# Motor_Control_-_Top_Level.net
KiCad netlist of a schematic drawn in Altium Designer
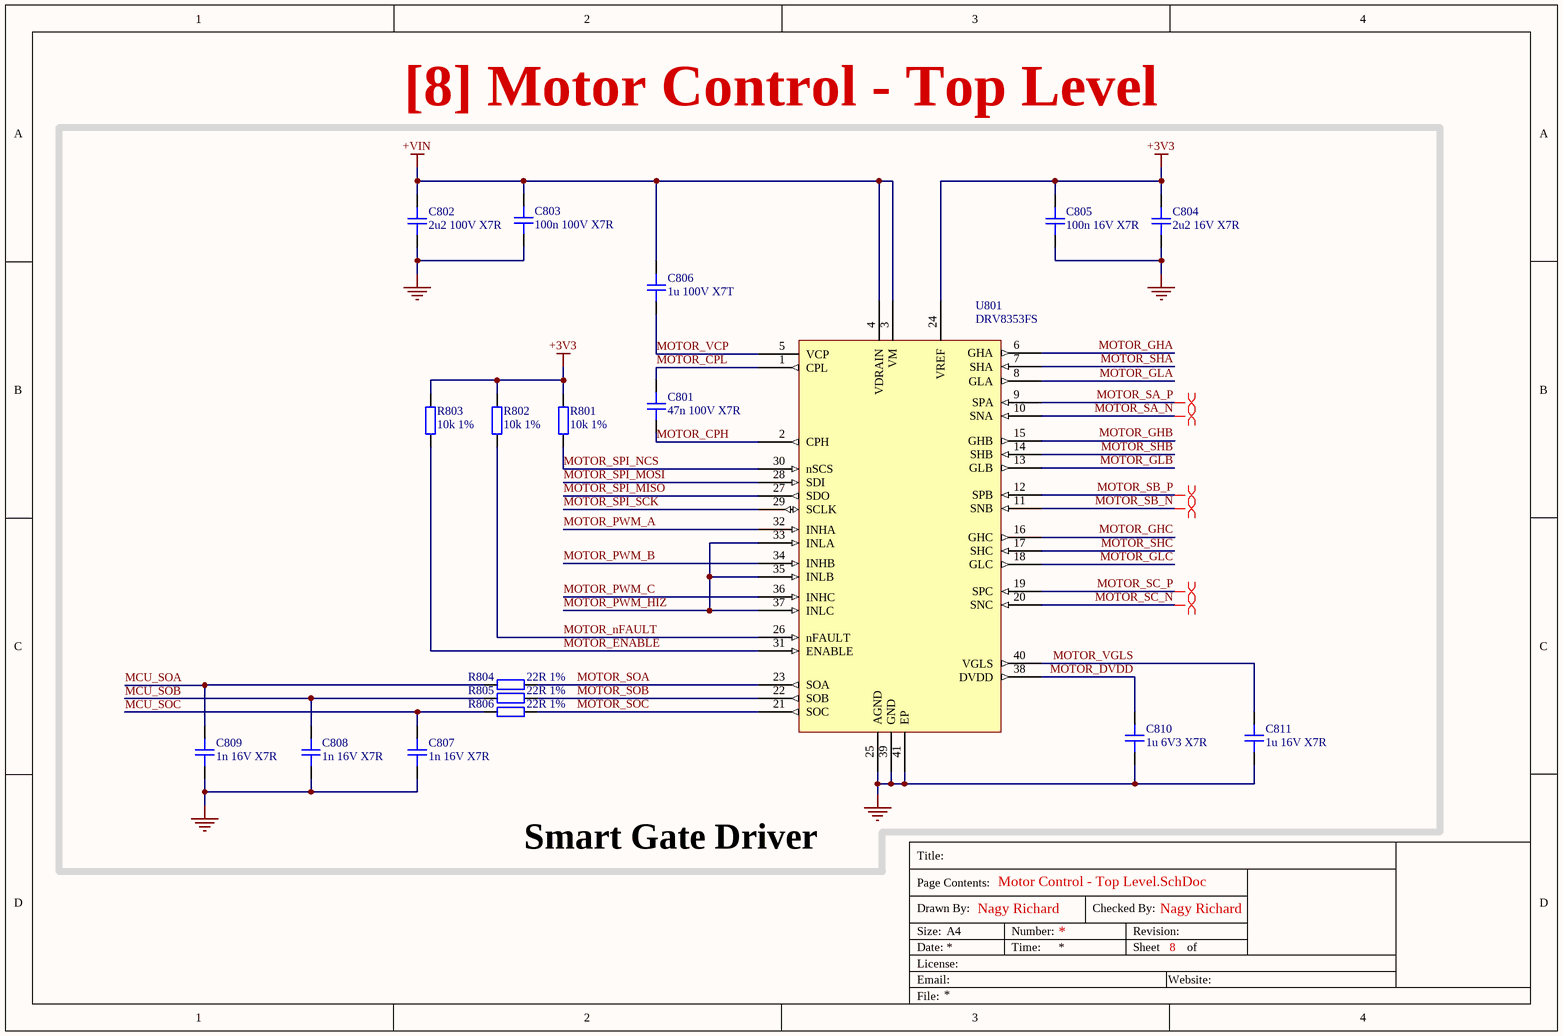
[diagram p0: Motor Control - Top Level.SchDoc]

(export (version "E")
  (design (tool "Eeschema 10.0.6"))
  (components
    (comp (ref "C801")
      (value "47n 100V X7R")
      (footprint "CAP_0603")
      (description "Capacitor SMD 0603")
      (fields
        (field (name "MANUFACTURER") "YAGEO")
        (field (name "MANUFACTURER PART NUMBER") "CC0603KRX7R0BB473")
      )
      (libsource (lib "Schematic-Lib-PhilsLab") (part "CAP_0603"))
    )
    (comp (ref "C802")
      (value "2u2 100V X7R")
      (footprint "CAP_0805")
      (description "Capacitor SMD 0805")
      (fields
        (field (name "MANUFACTURER") "HRE")
        (field (name "MANUFACTURER PART NUMBER") "CGA0805X7R225K101MT")
      )
      (libsource (lib "Schematic-Lib-PhilsLab") (part "CAP_0805"))
    )
    (comp (ref "C803")
      (value "100n 100V X7R")
      (footprint "CAP_0603")
      (description "Capacitor SMD 0603")
      (fields
        (field (name "MANUFACTURER") "YAGEO")
        (field (name "MANUFACTURER PART NUMBER") "AC0603KRX7R0BB104")
      )
      (libsource (lib "Schematic-Lib-PhilsLab") (part "CAP_0603"))
    )
    (comp (ref "C804")
      (value "2u2 16V X7R")
      (footprint "CAP_0603")
      (description "Capacitor SMD 0603")
      (fields
        (field (name "MANUFACTURER") "YAGEO")
        (field (name "MANUFACTURER PART NUMBER") "CC0603KRX7R7BB225")
      )
      (libsource (lib "Schematic-Lib-PhilsLab") (part "CAP_0603"))
    )
    (comp (ref "C805")
      (value "100n 16V X7R")
      (footprint "CAP_0402")
      (description "Capacitor SMD 0402")
      (fields
        (field (name "MANUFACTURER") "YAGEO")
        (field (name "MANUFACTURER PART NUMBER") "CC0402JRX7R7BB104")
      )
      (libsource (lib "Schematic-Lib-PhilsLab") (part "CAP_0402"))
    )
    (comp (ref "C806")
      (value "1u 100V X7T")
      (footprint "CAP_0603")
      (description "Capacitor SMD 0603")
      (fields
        (field (name "MANUFACTURER") "Murata Electronics")
        (field (name "MANUFACTURER PART NUMBER") "GRM188D72A105KE01D")
      )
      (libsource (lib "Schematic-Lib-PhilsLab") (part "CAP_0603"))
    )
    (comp (ref "C807")
      (value "1n 16V X7R")
      (footprint "CAP_0402")
      (description "Capacitor SMD 0402")
      (fields
        (field (name "MANUFACTURER") "YAGEO")
        (field (name "MANUFACTURER PART NUMBER") "AC0402KRX7R7BB102")
      )
      (libsource (lib "Schematic-Lib-PhilsLab") (part "CAP_0402"))
    )
    (comp (ref "C808")
      (value "1n 16V X7R")
      (footprint "CAP_0402")
      (description "Capacitor SMD 0402")
      (fields
        (field (name "MANUFACTURER") "YAGEO")
        (field (name "MANUFACTURER PART NUMBER") "AC0402KRX7R7BB102")
      )
      (libsource (lib "Schematic-Lib-PhilsLab") (part "CAP_0402"))
    )
    (comp (ref "C809")
      (value "1n 16V X7R")
      (footprint "CAP_0402")
      (description "Capacitor SMD 0402")
      (fields
        (field (name "MANUFACTURER") "YAGEO")
        (field (name "MANUFACTURER PART NUMBER") "AC0402KRX7R7BB102")
      )
      (libsource (lib "Schematic-Lib-PhilsLab") (part "CAP_0402"))
    )
    (comp (ref "C810")
      (value "1u 6V3 X7R")
      (footprint "CAP_0603")
      (description "Capacitor SMD 0603")
      (fields
        (field (name "MANUFACTURER") "YAGEO")
        (field (name "MANUFACTURER PART NUMBER") "CC0603KRX7R5BB105")
      )
      (libsource (lib "Schematic-Lib-PhilsLab") (part "CAP_0603"))
    )
    (comp (ref "C811")
      (value "1u 16V X7R")
      (footprint "CAP_0603")
      (description "Capacitor SMD 0603")
      (fields
        (field (name "MANUFACTURER") "Murata Electronics")
        (field (name "MANUFACTURER PART NUMBER") "GRM188R71C105ME15D")
      )
      (libsource (lib "Schematic-Lib-PhilsLab") (part "CAP_0603"))
    )
    (comp (ref "R801")
      (value "10k 1%")
      (footprint "RES_0402")
      (description "Resistor SMD 0402")
      (fields
        (field (name "MANUFACTURER") "PANASONIC")
        (field (name "MANUFACTURER PART NUMBER") "ERJPA2F1002X")
      )
      (libsource (lib "Schematic-Lib-PhilsLab") (part "RES_0402"))
    )
    (comp (ref "R802")
      (value "10k 1%")
      (footprint "RES_0402")
      (description "Resistor SMD 0402")
      (fields
        (field (name "MANUFACTURER") "PANASONIC")
        (field (name "MANUFACTURER PART NUMBER") "ERJPA2F1002X")
      )
      (libsource (lib "Schematic-Lib-PhilsLab") (part "RES_0402"))
    )
    (comp (ref "R803")
      (value "10k 1%")
      (footprint "RES_0402")
      (description "Resistor SMD 0402")
      (fields
        (field (name "MANUFACTURER") "PANASONIC")
        (field (name "MANUFACTURER PART NUMBER") "ERJPA2F1002X")
      )
      (libsource (lib "Schematic-Lib-PhilsLab") (part "RES_0402"))
    )
    (comp (ref "R804")
      (value "22R 1%")
      (footprint "RES_0402")
      (description "Resistor SMD 0402")
      (fields
        (field (name "MANUFACTURER") "PANASONIC")
        (field (name "MANUFACTURER PART NUMBER") "ERJPA2F22R0X")
      )
      (libsource (lib "Schematic-Lib-PhilsLab") (part "RES_0402"))
    )
    (comp (ref "R805")
      (value "22R 1%")
      (footprint "RES_0402")
      (description "Resistor SMD 0402")
      (fields
        (field (name "MANUFACTURER") "PANASONIC")
        (field (name "MANUFACTURER PART NUMBER") "ERJPA2F22R0X")
      )
      (libsource (lib "Schematic-Lib-PhilsLab") (part "RES_0402"))
    )
    (comp (ref "R806")
      (value "22R 1%")
      (footprint "RES_0402")
      (description "Resistor SMD 0402")
      (fields
        (field (name "MANUFACTURER") "PANASONIC")
        (field (name "MANUFACTURER PART NUMBER") "ERJPA2F22R0X")
      )
      (libsource (lib "Schematic-Lib-PhilsLab") (part "RES_0402"))
    )
    (comp (ref "U801")
      (value "DRV8353FS")
      (footprint "QFN50P600X600X80-41N-D")
      (description "DRV835xF 100-V Three-Phase Smart Gate Driver")
      (libsource (lib "Schematic-Lib-PhilsLab") (part "DRV8353FS"))
    )
  )
  (nets
    (net (code "1") (name "+3V3") (class "Default")
      (node (ref "C804") (pin "2") (pinfunction "2_2") (pintype "passive"))
      (node (ref "C805") (pin "2") (pinfunction "2_2") (pintype "passive"))
      (node (ref "R801") (pin "2") (pinfunction "2_2") (pintype "passive"))
      (node (ref "R802") (pin "2") (pinfunction "2_2") (pintype "passive"))
      (node (ref "R803") (pin "2") (pinfunction "2_2") (pintype "passive"))
      (node (ref "U801") (pin "24") (pinfunction "VREF_24") (pintype "power_in"))
    )
    (net (code "2") (name "+VIN") (class "Default")
      (node (ref "C802") (pin "2") (pinfunction "2_2") (pintype "passive"))
      (node (ref "C803") (pin "2") (pinfunction "2_2") (pintype "passive"))
      (node (ref "C806") (pin "2") (pinfunction "2_2") (pintype "passive"))
      (node (ref "U801") (pin "3") (pinfunction "VM_3") (pintype "power_in"))
      (node (ref "U801") (pin "4") (pinfunction "VDRAIN_4") (pintype "power_in"))
    )
    (net (code "3") (name "/MCU_SOA") (class "Default")
      (node (ref "C809") (pin "2") (pinfunction "2_2") (pintype "passive"))
      (node (ref "R804") (pin "2") (pinfunction "2_2") (pintype "passive"))
    )
    (net (code "4") (name "/MCU_SOB") (class "Default")
      (node (ref "C808") (pin "2") (pinfunction "2_2") (pintype "passive"))
      (node (ref "R805") (pin "2") (pinfunction "2_2") (pintype "passive"))
    )
    (net (code "5") (name "/MCU_SOC") (class "Default")
      (node (ref "C807") (pin "2") (pinfunction "2_2") (pintype "passive"))
      (node (ref "R806") (pin "2") (pinfunction "2_2") (pintype "passive"))
    )
    (net (code "6") (name "/MOTOR_CPH") (class "Default")
      (node (ref "C801") (pin "1") (pinfunction "1_1") (pintype "passive"))
      (node (ref "U801") (pin "2") (pinfunction "CPH_2") (pintype "output"))
    )
    (net (code "7") (name "/MOTOR_CPL") (class "Default")
      (node (ref "C801") (pin "2") (pinfunction "2_2") (pintype "passive"))
      (node (ref "U801") (pin "1") (pinfunction "CPL_1") (pintype "output"))
    )
    (net (code "8") (name "/MOTOR_DVDD") (class "Default")
      (node (ref "C810") (pin "2") (pinfunction "2_2") (pintype "passive"))
      (node (ref "U801") (pin "38") (pinfunction "DVDD_38") (pintype "output"))
    )
    (net (code "9") (name "/MOTOR_ENABLE") (class "Default")
      (node (ref "R803") (pin "1") (pinfunction "1_1") (pintype "passive"))
      (node (ref "U801") (pin "31") (pinfunction "ENABLE_31") (pintype "input"))
    )
    (net (code "10") (name "/MOTOR_GHA") (class "Default")
      (node (ref "U801") (pin "6") (pinfunction "GHA_6") (pintype "output"))
    )
    (net (code "11") (name "/MOTOR_GHB") (class "Default")
      (node (ref "U801") (pin "15") (pinfunction "GHB_15") (pintype "output"))
    )
    (net (code "12") (name "/MOTOR_GHC") (class "Default")
      (node (ref "U801") (pin "16") (pinfunction "GHC_16") (pintype "output"))
    )
    (net (code "13") (name "/MOTOR_GLA") (class "Default")
      (node (ref "U801") (pin "8") (pinfunction "GLA_8") (pintype "output"))
    )
    (net (code "14") (name "/MOTOR_GLB") (class "Default")
      (node (ref "U801") (pin "13") (pinfunction "GLB_13") (pintype "output"))
    )
    (net (code "15") (name "/MOTOR_GLC") (class "Default")
      (node (ref "U801") (pin "18") (pinfunction "GLC_18") (pintype "output"))
    )
    (net (code "16") (name "/MOTOR_PWM_A") (class "Default")
      (node (ref "U801") (pin "32") (pinfunction "INHA_32") (pintype "input"))
    )
    (net (code "17") (name "/MOTOR_PWM_B") (class "Default")
      (node (ref "U801") (pin "34") (pinfunction "INHB_34") (pintype "input"))
    )
    (net (code "18") (name "/MOTOR_PWM_C") (class "Default")
      (node (ref "U801") (pin "36") (pinfunction "INHC_36") (pintype "input"))
    )
    (net (code "19") (name "/MOTOR_PWM_HIZ") (class "Default")
      (node (ref "U801") (pin "33") (pinfunction "INLA_33") (pintype "input"))
      (node (ref "U801") (pin "35") (pinfunction "INLB_35") (pintype "input"))
      (node (ref "U801") (pin "37") (pinfunction "INLC_37") (pintype "input"))
    )
    (net (code "20") (name "/MOTOR_SA_N") (class "Default")
      (node (ref "U801") (pin "10") (pinfunction "SNA_10") (pintype "input"))
    )
    (net (code "21") (name "/MOTOR_SA_P") (class "Default")
      (node (ref "U801") (pin "9") (pinfunction "SPA_9") (pintype "input"))
    )
    (net (code "22") (name "/MOTOR_SB_N") (class "Default")
      (node (ref "U801") (pin "11") (pinfunction "SNB_11") (pintype "input"))
    )
    (net (code "23") (name "/MOTOR_SB_P") (class "Default")
      (node (ref "U801") (pin "12") (pinfunction "SPB_12") (pintype "input"))
    )
    (net (code "24") (name "/MOTOR_SC_N") (class "Default")
      (node (ref "U801") (pin "20") (pinfunction "SNC_20") (pintype "input"))
    )
    (net (code "25") (name "/MOTOR_SC_P") (class "Default")
      (node (ref "U801") (pin "19") (pinfunction "SPC_19") (pintype "input"))
    )
    (net (code "26") (name "/MOTOR_SHA") (class "Default")
      (node (ref "U801") (pin "7") (pinfunction "SHA_7") (pintype "input"))
    )
    (net (code "27") (name "/MOTOR_SHB") (class "Default")
      (node (ref "U801") (pin "14") (pinfunction "SHB_14") (pintype "input"))
    )
    (net (code "28") (name "/MOTOR_SHC") (class "Default")
      (node (ref "U801") (pin "17") (pinfunction "SHC_17") (pintype "input"))
    )
    (net (code "29") (name "/MOTOR_SOA") (class "Default")
      (node (ref "R804") (pin "1") (pinfunction "1_1") (pintype "passive"))
      (node (ref "U801") (pin "23") (pinfunction "SOA_23") (pintype "output"))
    )
    (net (code "32") (name "/MOTOR_SOB") (class "Default")
      (node (ref "R805") (pin "1") (pinfunction "1_1") (pintype "passive"))
      (node (ref "U801") (pin "22") (pinfunction "SOB_22") (pintype "output"))
    )
    (net (code "33") (name "/MOTOR_SOC") (class "Default")
      (node (ref "R806") (pin "1") (pinfunction "1_1") (pintype "passive"))
      (node (ref "U801") (pin "21") (pinfunction "SOC_21") (pintype "output"))
    )
    (net (code "34") (name "/MOTOR_SPI_MISO") (class "Default")
      (node (ref "U801") (pin "27") (pinfunction "SDO_27") (pintype "output"))
    )
    (net (code "35") (name "/MOTOR_SPI_MOSI") (class "Default")
      (node (ref "U801") (pin "28") (pinfunction "SDI_28") (pintype "input"))
    )
    (net (code "36") (name "/MOTOR_SPI_NCS") (class "Default")
      (node (ref "R801") (pin "1") (pinfunction "1_1") (pintype "passive"))
      (node (ref "U801") (pin "30") (pinfunction "nSCS_30") (pintype "input"))
    )
    (net (code "37") (name "/MOTOR_SPI_SCK") (class "Default")
      (node (ref "U801") (pin "29") (pinfunction "SCLK_29") (pintype "bidirectional"))
    )
    (net (code "38") (name "/MOTOR_VCP") (class "Default")
      (node (ref "C806") (pin "1") (pinfunction "1_1") (pintype "passive"))
      (node (ref "U801") (pin "5") (pinfunction "VCP_5") (pintype "power_in"))
    )
    (net (code "39") (name "/MOTOR_VGLS") (class "Default")
      (node (ref "C811") (pin "2") (pinfunction "2_2") (pintype "passive"))
      (node (ref "U801") (pin "40") (pinfunction "VGLS_40") (pintype "output"))
    )
    (net (code "40") (name "/MOTOR_nFAULT") (class "Default")
      (node (ref "R802") (pin "1") (pinfunction "1_1") (pintype "passive"))
      (node (ref "U801") (pin "26") (pinfunction "nFAULT_26") (pintype "input"))
    )
    (net (code "41") (name "GND") (class "Default")
      (node (ref "C802") (pin "1") (pinfunction "1_1") (pintype "passive"))
      (node (ref "C803") (pin "1") (pinfunction "1_1") (pintype "passive"))
      (node (ref "C804") (pin "1") (pinfunction "1_1") (pintype "passive"))
      (node (ref "C805") (pin "1") (pinfunction "1_1") (pintype "passive"))
      (node (ref "C807") (pin "1") (pinfunction "1_1") (pintype "passive"))
      (node (ref "C808") (pin "1") (pinfunction "1_1") (pintype "passive"))
      (node (ref "C809") (pin "1") (pinfunction "1_1") (pintype "passive"))
      (node (ref "C810") (pin "1") (pinfunction "1_1") (pintype "passive"))
      (node (ref "C811") (pin "1") (pinfunction "1_1") (pintype "passive"))
      (node (ref "U801") (pin "25") (pinfunction "AGND_25") (pintype "passive"))
      (node (ref "U801") (pin "39") (pinfunction "GND_39") (pintype "passive"))
      (node (ref "U801") (pin "41") (pinfunction "EP_41") (pintype "passive"))
    )
  )
)
